# Power_Circuit_Schematic.net
KiCad netlist of a schematic drawn in Altium Designer
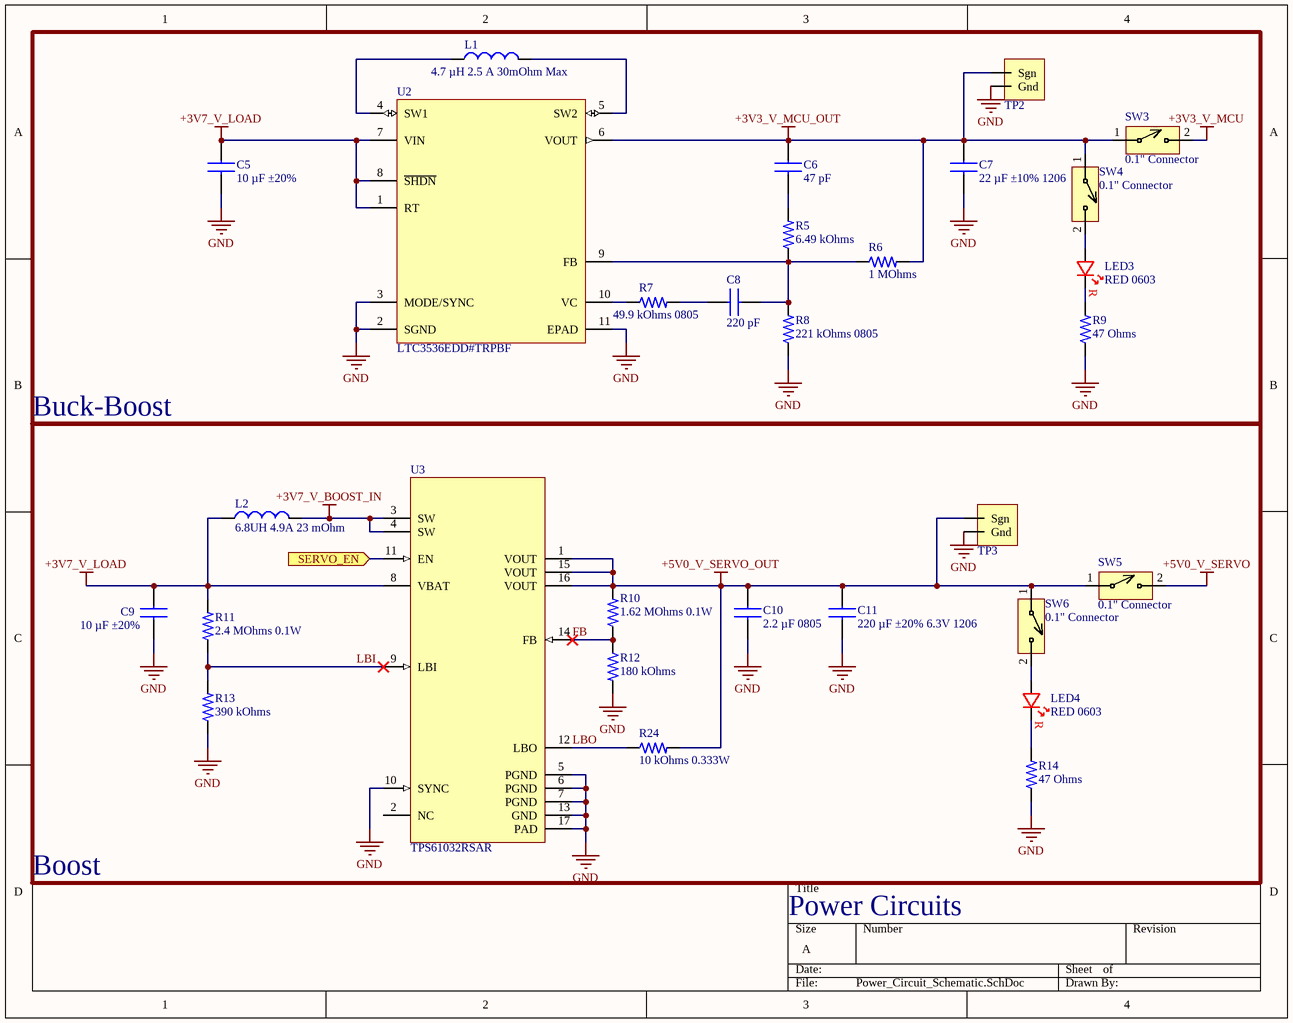
[diagram p0: Power_Circuit_Schematic.SchDoc]

(export (version "E")
  (design (tool "Eeschema 10.0.6"))
  (components
    (comp (ref "C5")
      (value "10 µF ±20%")
      (footprint "CAPC0603X10N-M")
      (description "0603 10 uF 16 V ±20% Tolerance X6S Surface Mount Multilayer Ceramic Capacitor")
      (fields
        (field (name "MANUFACTURER") "Murata")
        (field (name "MANUFACTURER PART NUMBER") "GRT188C81C106ME13D")
      )
      (libsource (lib "PartsLib") (part "GRT188C81C106ME13D"))
    )
    (comp (ref "C6")
      (value "47 pF")
      (footprint "CAPC0603X09N")
      (description "Cap Ceramic 47pF 16V C0G 5% SMD 0603 125°C Paper T/R")
      (fields
        (field (name "MANUFACTURER") "KEMET")
        (field (name "MANUFACTURER PART NUMBER") "C0603C470J4GAC7867")
      )
      (libsource (lib "PartsLib") (part "C0603C470J4GAC7867"))
    )
    (comp (ref "C7")
      (value "22 µF ±10% 1206")
      (footprint "CAPC1206X18N")
      (description "1206 22 uF 16 V ±10% Tolerance X6S Multilayer Ceramic Capacitor")
      (fields
        (field (name "MANUFACTURER") "Murata")
        (field (name "MANUFACTURER PART NUMBER") "GRT31CC81C226KE01L")
      )
      (libsource (lib "PartsLib") (part "GRT31CC81C226KE01L"))
    )
    (comp (ref "C8")
      (value "220 pF")
      (footprint "CAPC0603X09N")
      (description "Cap Cer 220PF 16V C0G/NP0 0603")
      (fields
        (field (name "MANUFACTURER") "KEMET")
        (field (name "MANUFACTURER PART NUMBER") "C0603C221J4GAC7867")
      )
      (libsource (lib "PartsLib") (part "C0603C221J4GAC7867"))
    )
    (comp (ref "C9")
      (value "10 µF ±20%")
      (footprint "CAPC0603X10N-M")
      (description "0603 10 uF 16 V ±20% Tolerance X6S Surface Mount Multilayer Ceramic Capacitor")
      (fields
        (field (name "MANUFACTURER") "Murata")
        (field (name "MANUFACTURER PART NUMBER") "GRT188C81C106ME13D")
      )
      (libsource (lib "PartsLib") (part "GRT188C81C106ME13D"))
    )
    (comp (ref "C10")
      (value "2.2 µF 0805")
      (footprint "CAPC0805X12N")
      (description "Cap Cer 0805 2.2UF 16V X7R 5%")
      (fields
        (field (name "MANUFACTURER") "KEMET")
        (field (name "MANUFACTURER PART NUMBER") "C0805X225J4RECAUTO")
      )
      (libsource (lib "PartsLib") (part "C0805X225J4RECAUTO"))
    )
    (comp (ref "C11")
      (value "220 µF ±20% 6.3V 1206")
      (footprint "CAPC1206X19N")
      (description "1206 220 uF 6.3 V ±20% Tolernace X5R Multilayer Ceramic Capacitor")
      (fields
        (field (name "MANUFACTURER") "Murata")
        (field (name "MANUFACTURER PART NUMBER") "GRM31CR60J227ME11L")
      )
      (libsource (lib "PartsLib") (part "GRM31CR60J227ME11L"))
    )
    (comp (ref "L1")
      (value "4.7 µH 2.5 A 30mOhm Max")
      (footprint "INDP7272X45N")
      (description "Ind Power Shielded 4.7uH 20% 100KHz Ferrite 2.5A Blister T/R")
      (fields
        (field (name "MANUFACTURER") "TDK EPCOS")
        (field (name "MANUFACTURER PART NUMBER") "B82472G6472M000")
      )
      (libsource (lib "PartsLib") (part "B82472G6472M000"))
    )
    (comp (ref "L2")
      (value "6.8UH 4.9A 23 mOhm")
      (footprint "INDP120120X45N")
      (description "Inductor Power Shielded Drum Core 6.8uH 20% 100KHz Ferrite 4.9A 23mOhm DCR T/R")
      (fields
        (field (name "MANUFACTURER") "Sumida")
        (field (name "MANUFACTURER PART NUMBER") "CDRH124NP-6R8MC")
      )
      (libsource (lib "PartsLib") (part "CDRH124NP-6R8MC"))
    )
    (comp (ref "LED3")
      (value "RED 0603")
      (footprint "DIOC0603X06N")
      (description "0603(H=0.65mm) 红色 λD=631nm VR=5V VF=2.0V~2.4V IF=20mA PD=75mW")
      (fields
        (field (name "MANUFACTURER") "Vishay Lite-On")
        (field (name "MANUFACTURER PART NUMBER") "LTST-C191KRKT")
      )
      (libsource (lib "PartsLib") (part "LTST-C191KRKT"))
    )
    (comp (ref "LED4")
      (value "RED 0603")
      (footprint "DIOC0603X06N")
      (description "0603(H=0.65mm) 红色 λD=631nm VR=5V VF=2.0V~2.4V IF=20mA PD=75mW")
      (fields
        (field (name "MANUFACTURER") "Vishay Lite-On")
        (field (name "MANUFACTURER PART NUMBER") "LTST-C191KRKT")
      )
      (libsource (lib "PartsLib") (part "LTST-C191KRKT"))
    )
    (comp (ref "R5")
      (value "6.49 kOhms")
      (footprint "RESC0603X05N")
      (description "RES SMD 6.49K OHM 1% 1/4W 0603")
      (fields
        (field (name "MANUFACTURER") "Vishay Dale")
        (field (name "MANUFACTURER PART NUMBER") "RCS06036K49FKEA")
      )
      (libsource (lib "PartsLib") (part "RCS06036K49FKEA"))
    )
    (comp (ref "R6")
      (value "1 MOhms")
      (footprint "RESC0603X06N-BB")
      (description "Resistor, ResHighPower 0603 1M 1% 1/4W TC100")
      (fields
        (field (name "MANUFACTURER") "Bourns")
        (field (name "MANUFACTURER PART NUMBER") "CMP0603-FX-1004ELF")
      )
      (libsource (lib "PartsLib") (part "CMP0603-FX-1004ELF"))
    )
    (comp (ref "R7")
      (value "49.9 kOhms 0805")
      (footprint "RESC0805X05N")
      (description "Res Thick Film 0805 49.9K Ohm 1% 0.25W(1/4W) ±100ppm/C Pad SMD Automotive T/R")
      (fields
        (field (name "MANUFACTURER") "Vishay Dale")
        (field (name "MANUFACTURER PART NUMBER") "RCC080549K9FKEA")
      )
      (libsource (lib "PartsLib") (part "RCC080549K9FKEA"))
    )
    (comp (ref "R8")
      (value "221 kOhms 0805")
      (footprint "RESC0805X06N")
      (description "Res Thick Film 0805 221K Ohm 1% 0.25W(1/4W) ±100ppm/C Pad SMD Automotive T/R")
      (fields
        (field (name "MANUFACTURER") "KOA Speer")
        (field (name "MANUFACTURER PART NUMBER") "RK73H2ATTD2213F")
      )
      (libsource (lib "PartsLib") (part "RK73H2ATTD2213F"))
    )
    (comp (ref "R9")
      (value "47 Ohms")
      (footprint "RESC0603X06N")
      (description "Res Thick Film 0603 47 Ohm 1% 1/10W ±100ppm/°C Molded SMD Paper T/R")
      (fields
        (field (name "MANUFACTURER") "Vishay Semiconductors")
        (field (name "MANUFACTURER PART NUMBER") "CRCW060347R0FKEAC")
      )
      (libsource (lib "PartsLib") (part "CRCW060347R0FKEAC"))
    )
    (comp (ref "R10")
      (value "1.62 MOhms 0.1W")
      (footprint "RESC0603X05N-2")
      (description "Res Thick Film 0603 1.62M Ohm 1% 1/10W ±200ppm/°C Molded SMD SMD Paper T/R")
      (fields
        (field (name "MANUFACTURER") "Stackpole Electronics")
        (field (name "MANUFACTURER PART NUMBER") "RMCF0603FT1M62")
      )
      (libsource (lib "PartsLib") (part "RMCF0603FT1M62"))
    )
    (comp (ref "R11")
      (value "2.4 MOhms 0.1W")
      (footprint "RESC0603X05N-2")
      (description "Res Thick Film 0603 2.4M Ohm 1% 1/10W ±200ppm/°C Molded SMD SMD Paper T/R")
      (fields
        (field (name "MANUFACTURER") "Stackpole Electronics")
        (field (name "MANUFACTURER PART NUMBER") "RMCF0603FT2M40")
      )
      (libsource (lib "PartsLib") (part "RMCF0603FT2M40"))
    )
    (comp (ref "R12")
      (value "180 kOhms")
      (footprint "RESC0603X05N")
      (description "RES SMD 180K OHM 1% 1/4W 0603")
      (fields
        (field (name "MANUFACTURER") "Vishay Dale")
        (field (name "MANUFACTURER PART NUMBER") "RCS0603180KFKEA")
      )
      (libsource (lib "PartsLib") (part "RCS0603180KFKEA"))
    )
    (comp (ref "R13")
      (value "390 kOhms")
      (footprint "RESC0603X05N")
      (description "RES SMD 390K OHM 1% 1/4W 0603")
      (fields
        (field (name "MANUFACTURER") "Vishay Dale")
        (field (name "MANUFACTURER PART NUMBER") "RCS0603390KFKEA")
      )
      (libsource (lib "PartsLib") (part "RCS0603390KFKEA"))
    )
    (comp (ref "R14")
      (value "47 Ohms")
      (footprint "RESC0603X06N")
      (description "Res Thick Film 0603 47 Ohm 1% 1/10W ±100ppm/°C Molded SMD Paper T/R")
      (fields
        (field (name "MANUFACTURER") "Vishay Semiconductors")
        (field (name "MANUFACTURER PART NUMBER") "CRCW060347R0FKEAC")
      )
      (libsource (lib "PartsLib") (part "CRCW060347R0FKEAC"))
    )
    (comp (ref "R24")
      (value "10 kOhms 0.333W")
      (footprint "RESC0603X06N")
      (description "Res Thick Film 0603 10K Ohm 1% 0.33W(1/3W) ±100ppm/°C Pad SMD Automotive T/R")
      (fields
        (field (name "MANUFACTURER") "Vishay")
        (field (name "MANUFACTURER PART NUMBER") "CRCW060310K0FKEAHP")
      )
      (libsource (lib "PartsLib") (part "CRCW060310K0FKEAHP"))
    )
    (comp (ref "SW3")
      (value "0.1\" Connector")
      (footprint "2Pin-Header-Conn")
      (description "PBT/Brass 2 Position 2.54 mm Pitch Straight Male Breakaway Header")
      (fields
        (field (name "MANUFACTURER") "Sullins")
        (field (name "MANUFACTURER PART NUMBER") "PRPC001DAAN-RC")
      )
      (libsource (lib "PartsLib") (part "PRPC001DAAN-RC"))
    )
    (comp (ref "SW4")
      (value "0.1\" Connector")
      (footprint "2Pin-Header-Conn")
      (description "PBT/Brass 2 Position 2.54 mm Pitch Straight Male Breakaway Header")
      (fields
        (field (name "MANUFACTURER") "Sullins")
        (field (name "MANUFACTURER PART NUMBER") "PRPC001DAAN-RC")
      )
      (libsource (lib "") (part "PRPC001DAAN-RC_1"))
    )
    (comp (ref "SW5")
      (value "0.1\" Connector")
      (footprint "2Pin-Header-Conn")
      (description "PBT/Brass 2 Position 2.54 mm Pitch Straight Male Breakaway Header")
      (fields
        (field (name "MANUFACTURER") "Sullins")
        (field (name "MANUFACTURER PART NUMBER") "PRPC001DAAN-RC")
      )
      (libsource (lib "PartsLib") (part "PRPC001DAAN-RC"))
    )
    (comp (ref "SW6")
      (value "0.1\" Connector")
      (footprint "2Pin-Header-Conn")
      (description "PBT/Brass 2 Position 2.54 mm Pitch Straight Male Breakaway Header")
      (fields
        (field (name "MANUFACTURER") "Sullins")
        (field (name "MANUFACTURER PART NUMBER") "PRPC001DAAN-RC")
      )
      (libsource (lib "") (part "PRPC001DAAN-RC_1"))
    )
    (comp (ref "TP2")
      (value "10x Probe TP")
      (footprint "TP10x_Probe")
      (description "Test Point 300 mil centers")
      (libsource (lib "PartsLib") (part "TP_10x_Probe"))
    )
    (comp (ref "TP3")
      (value "10x Probe TP")
      (footprint "TP10x_Probe")
      (description "Test Point 300 mil centers")
      (libsource (lib "PartsLib") (part "TP_10x_Probe"))
    )
    (comp (ref "U2")
      (value "LTC3536EDD#TRPBF")
      (footprint "SON50P300X80_HS-11N")
      (description "Dp-Swreg/Monolithic 1A Low Noise, Buck-Boost Dc/Dc Converter")
      (fields (field (name "MANUFACTURER") "Analog Devices / Linear Technology"))
      (libsource (lib "PartsLib") (part "LTC3536EDD#TRPBF"))
    )
    (comp (ref "U3")
      (value "TPS61032RSAR")
      (footprint "QFN65P400X400X100_HS-17N")
      (description "5-V Output, 1-A, 96% Efficient Boost Converter w/20uA Iq in TSSOP-16 16-QFN -40 to 85")
      (fields (field (name "MANUFACTURER") "Texas Instruments"))
      (libsource (lib "PartsLib") (part "TPS61032RSAR"))
    )
  )
  (nets
    (net (code "1") (name "+3V3_V_MCU") (class "Default")
      (node (ref "SW3") (pin "2") (pinfunction "2_2") (pintype "passive"))
    )
    (net (code "2") (name "+3V3_V_MCU_OUT") (class "Default")
      (node (ref "C6") (pin "1") (pinfunction "1_1") (pintype "passive"))
      (node (ref "C7") (pin "1") (pinfunction "1_1") (pintype "passive"))
      (node (ref "R6") (pin "2") (pinfunction "2_2") (pintype "passive"))
      (node (ref "SW3") (pin "1") (pinfunction "1_1") (pintype "passive"))
      (node (ref "SW4") (pin "1") (pinfunction "1_1") (pintype "passive"))
      (node (ref "TP2") (pin "1") (pinfunction "Sgn_1") (pintype "passive"))
      (node (ref "U2") (pin "6") (pinfunction "VOUT_6") (pintype "output"))
    )
    (net (code "3") (name "+3V7_V_BOOST_IN") (class "Default")
      (node (ref "L2") (pin "2") (pinfunction "2_2") (pintype "passive"))
      (node (ref "U3") (pin "3") (pinfunction "SW_3") (pintype "power_in"))
      (node (ref "U3") (pin "4") (pinfunction "SW_4") (pintype "power_in"))
    )
    (net (code "4") (name "+3V7_V_LOAD") (class "Default")
      (node (ref "C5") (pin "1") (pinfunction "1_1") (pintype "passive"))
      (node (ref "C9") (pin "1") (pinfunction "1_1") (pintype "passive"))
      (node (ref "L2") (pin "1") (pinfunction "1_1") (pintype "passive"))
      (node (ref "R11") (pin "2") (pinfunction "2_2") (pintype "passive"))
      (node (ref "U2") (pin "1") (pinfunction "RT_1") (pintype "passive"))
      (node (ref "U2") (pin "7") (pinfunction "VIN_7") (pintype "passive"))
      (node (ref "U2") (pin "8") (pinfunction "~{SHDN}_8") (pintype "passive"))
      (node (ref "U3") (pin "8") (pinfunction "VBAT_8") (pintype "power_in"))
    )
    (net (code "5") (name "+5V0_V_SERVO") (class "Default")
      (node (ref "SW5") (pin "2") (pinfunction "2_2") (pintype "passive"))
    )
    (net (code "6") (name "+5V0_V_SERVO_OUT") (class "Default")
      (node (ref "C10") (pin "1") (pinfunction "1_1") (pintype "passive"))
      (node (ref "C11") (pin "1") (pinfunction "1_1") (pintype "passive"))
      (node (ref "R10") (pin "2") (pinfunction "2_2") (pintype "passive"))
      (node (ref "R24") (pin "2") (pinfunction "2_2") (pintype "passive"))
      (node (ref "SW5") (pin "1") (pinfunction "1_1") (pintype "passive"))
      (node (ref "SW6") (pin "1") (pinfunction "1_1") (pintype "passive"))
      (node (ref "TP3") (pin "1") (pinfunction "Sgn_1") (pintype "passive"))
      (node (ref "U3") (pin "1") (pinfunction "VOUT_1") (pintype "power_in"))
      (node (ref "U3") (pin "15") (pinfunction "VOUT_15") (pintype "power_in"))
      (node (ref "U3") (pin "16") (pinfunction "VOUT_16") (pintype "power_in"))
    )
    (net (code "7") (name "/FB") (class "Default")
      (node (ref "R10") (pin "1") (pinfunction "1_1") (pintype "passive"))
      (node (ref "R12") (pin "1") (pinfunction "1_1") (pintype "passive"))
      (node (ref "U3") (pin "14") (pinfunction "FB_14") (pintype "input"))
    )
    (net (code "8") (name "/LBI") (class "Default")
      (node (ref "R11") (pin "1") (pinfunction "1_1") (pintype "passive"))
      (node (ref "R13") (pin "2") (pinfunction "2_2") (pintype "passive"))
      (node (ref "U3") (pin "9") (pinfunction "LBI_9") (pintype "input"))
    )
    (net (code "9") (name "/LBO") (class "Default")
      (node (ref "R24") (pin "1") (pinfunction "1_1") (pintype "passive"))
      (node (ref "U3") (pin "12") (pinfunction "LBO_12") (pintype "tri_state"))
    )
    (net (code "10") (name "/SERVO_EN") (class "Default")
      (node (ref "U3") (pin "11") (pinfunction "EN_11") (pintype "input"))
    )
    (net (code "11") (name "GND") (class "Default")
      (node (ref "C10") (pin "2") (pinfunction "2_2") (pintype "passive"))
      (node (ref "C11") (pin "2") (pinfunction "2_2") (pintype "passive"))
      (node (ref "C5") (pin "2") (pinfunction "2_2") (pintype "passive"))
      (node (ref "C7") (pin "2") (pinfunction "2_2") (pintype "passive"))
      (node (ref "C9") (pin "2") (pinfunction "2_2") (pintype "passive"))
      (node (ref "R12") (pin "2") (pinfunction "2_2") (pintype "passive"))
      (node (ref "R13") (pin "1") (pinfunction "1_1") (pintype "passive"))
      (node (ref "R14") (pin "1") (pinfunction "1_1") (pintype "passive"))
      (node (ref "R8") (pin "1") (pinfunction "1_1") (pintype "passive"))
      (node (ref "R9") (pin "1") (pinfunction "1_1") (pintype "passive"))
      (node (ref "TP2") (pin "2") (pinfunction "Gnd_2") (pintype "passive"))
      (node (ref "TP3") (pin "2") (pinfunction "Gnd_2") (pintype "passive"))
      (node (ref "U2") (pin "11") (pinfunction "EPAD_11") (pintype "passive"))
      (node (ref "U2") (pin "2") (pinfunction "SGND_2") (pintype "passive"))
      (node (ref "U2") (pin "3") (pinfunction "MODE/SYNC_3") (pintype "passive"))
      (node (ref "U3") (pin "10") (pinfunction "SYNC_10") (pintype "input"))
      (node (ref "U3") (pin "13") (pinfunction "GND_13") (pintype "power_in"))
      (node (ref "U3") (pin "17") (pinfunction "PAD_17") (pintype "power_in"))
      (node (ref "U3") (pin "5") (pinfunction "PGND_5") (pintype "power_in"))
      (node (ref "U3") (pin "6") (pinfunction "PGND_6") (pintype "power_in"))
      (node (ref "U3") (pin "7") (pinfunction "PGND_7") (pintype "power_in"))
    )
    (net (code "12") (name "Net-(C6-Pad2)") (class "Default")
      (node (ref "C6") (pin "2") (pinfunction "2_2") (pintype "passive"))
      (node (ref "R5") (pin "2") (pinfunction "2_2") (pintype "passive"))
    )
    (net (code "13") (name "Net-(C8-Pad2)") (class "Default")
      (node (ref "C8") (pin "2") (pinfunction "2_2") (pintype "passive"))
      (node (ref "R7") (pin "2") (pinfunction "2_2") (pintype "passive"))
    )
    (net (code "14") (name "Net-(LED3-PadA)") (class "Default")
      (node (ref "LED3") (pin "A") (pinfunction "A_A") (pintype "passive"))
      (node (ref "SW4") (pin "2") (pinfunction "2_2") (pintype "passive"))
    )
    (net (code "15") (name "Net-(LED3-PadC)") (class "Default")
      (node (ref "LED3") (pin "C") (pinfunction "C_C") (pintype "passive"))
      (node (ref "R9") (pin "2") (pinfunction "2_2") (pintype "passive"))
    )
    (net (code "16") (name "Net-(LED4-PadA)") (class "Default")
      (node (ref "LED4") (pin "A") (pinfunction "A_A") (pintype "passive"))
      (node (ref "SW6") (pin "2") (pinfunction "2_2") (pintype "passive"))
    )
    (net (code "17") (name "Net-(LED4-PadC)") (class "Default")
      (node (ref "LED4") (pin "C") (pinfunction "C_C") (pintype "passive"))
      (node (ref "R14") (pin "2") (pinfunction "2_2") (pintype "passive"))
    )
    (net (code "18") (name "Net-(U2-FB)") (class "Default")
      (node (ref "C8") (pin "1") (pinfunction "1_1") (pintype "passive"))
      (node (ref "R5") (pin "1") (pinfunction "1_1") (pintype "passive"))
      (node (ref "R6") (pin "1") (pinfunction "1_1") (pintype "passive"))
      (node (ref "R8") (pin "2") (pinfunction "2_2") (pintype "passive"))
      (node (ref "U2") (pin "9") (pinfunction "FB_9") (pintype "passive"))
    )
    (net (code "19") (name "Net-(U2-SW1)") (class "Default")
      (node (ref "L1") (pin "1") (pinfunction "1_1") (pintype "passive"))
      (node (ref "U2") (pin "4") (pinfunction "SW1_4") (pintype "bidirectional"))
    )
    (net (code "20") (name "Net-(U2-SW2)") (class "Default")
      (node (ref "L1") (pin "2") (pinfunction "2_2") (pintype "passive"))
      (node (ref "U2") (pin "5") (pinfunction "SW2_5") (pintype "bidirectional"))
    )
    (net (code "21") (name "Net-(U2-VC)") (class "Default")
      (node (ref "R7") (pin "1") (pinfunction "1_1") (pintype "passive"))
      (node (ref "U2") (pin "10") (pinfunction "VC_10") (pintype "passive"))
    )
    (net (code "22") (name "unconnected-(U3-NC-Pad2)") (class "Default")
      (node (ref "U3") (pin "2") (pinfunction "NC_2") (pintype "passive"))
    )
  )
)
